# Grove_-_UV_Sensor_v1_0.net
KiCad netlist of a schematic drawn in EAGLE
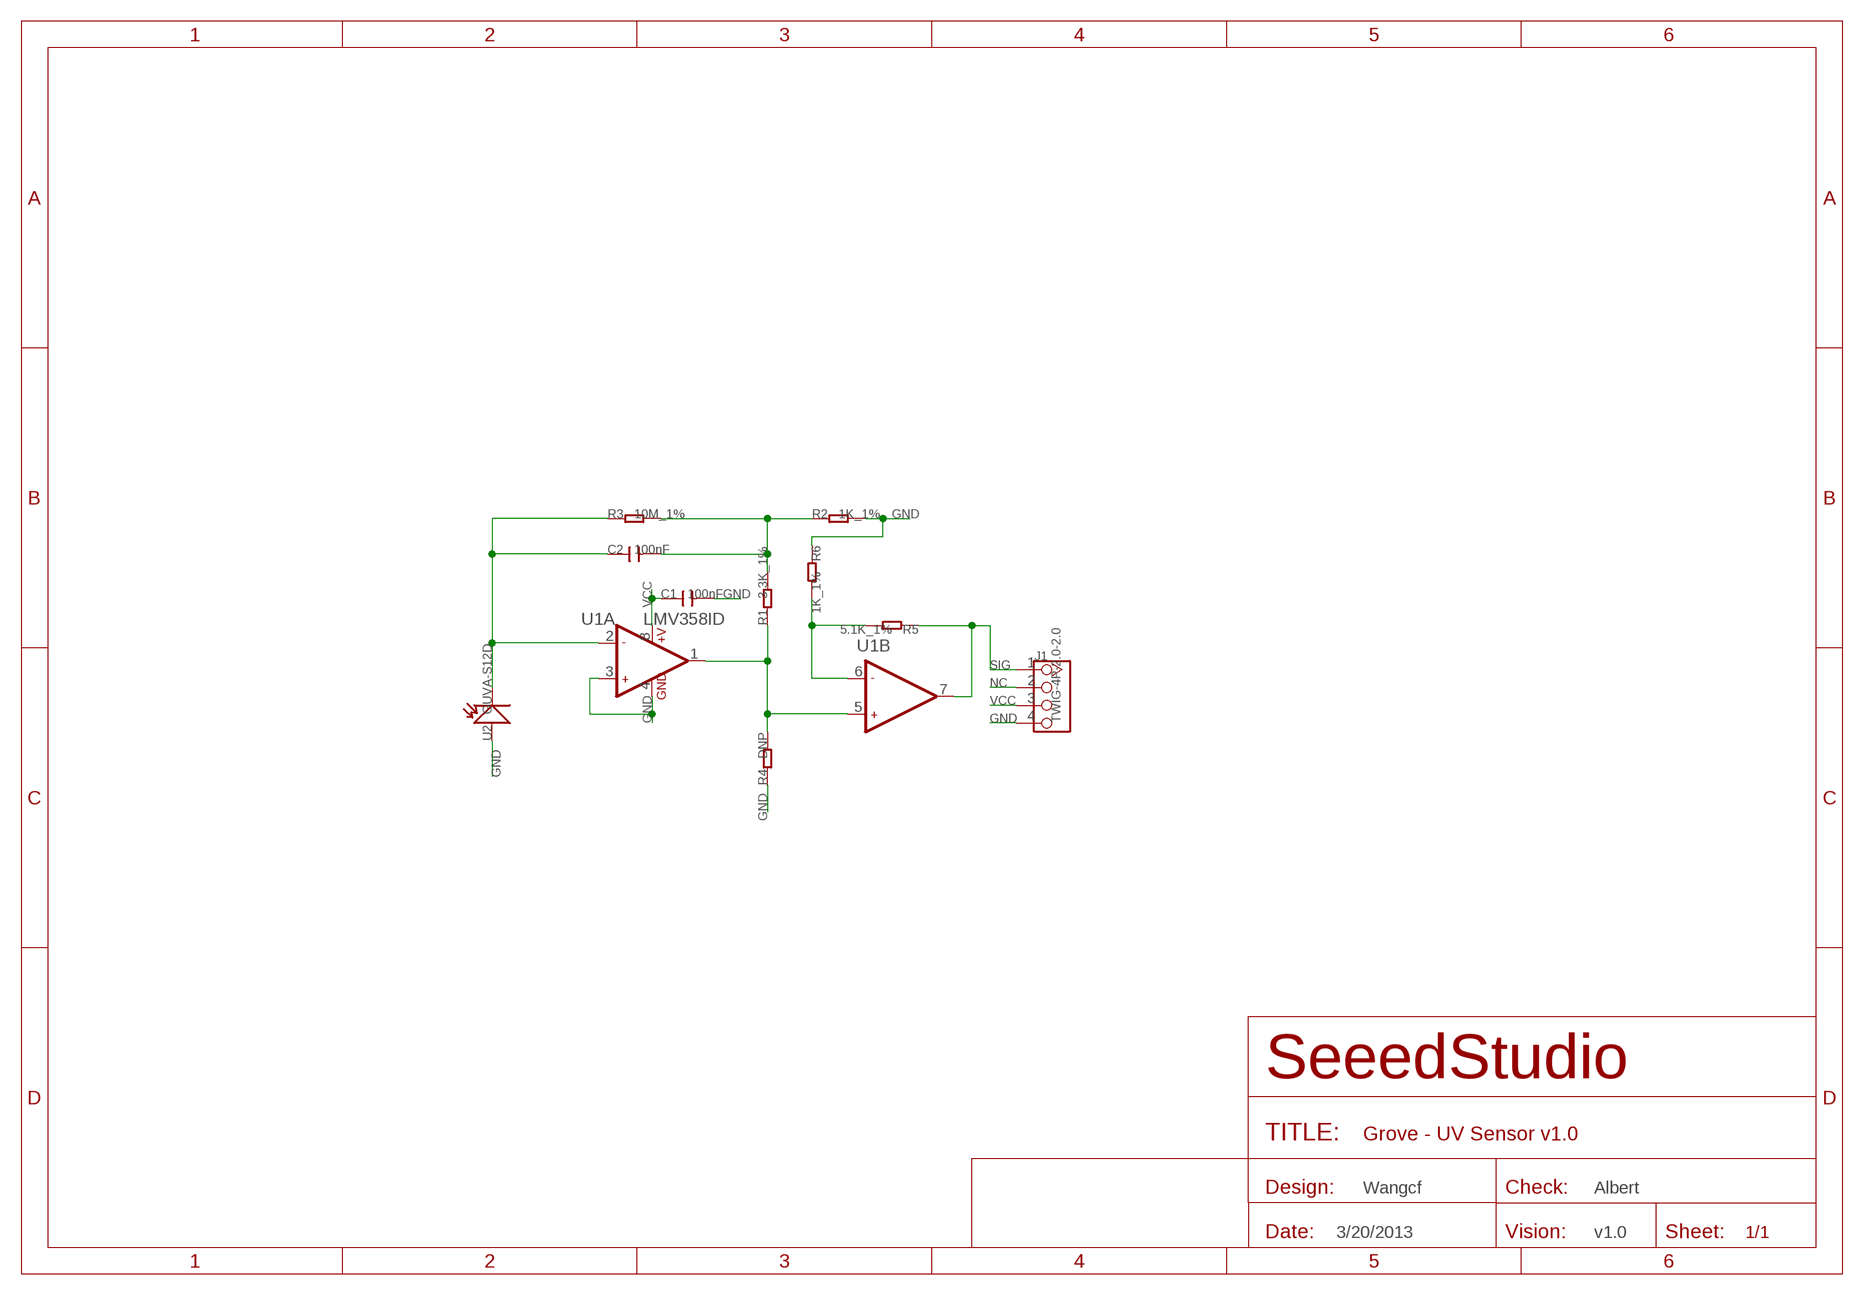
[diagram p0: schematic, sheet 1]

(export (version "E")
  (design (tool "Eeschema 10.0.6"))
  (components
    (comp (ref "C1")
      (value "100nF")
      (footprint "eagle-import:C0603")
      (libsource (lib "eagle-import") (part "C-0603"))
    )
    (comp (ref "C2")
      (value "100nF")
      (footprint "eagle-import:C0603")
      (libsource (lib "eagle-import") (part "C-0603"))
    )
    (comp (ref "J1")
      (value "TWIG-4P-2.0-2.0")
      (footprint "eagle-import:4P-2.0")
      (libsource (lib "eagle-import") (part "TWIG-4P-2.0-2.0"))
    )
    (comp (ref "R1")
      (value "3.3K_1%")
      (footprint "eagle-import:R0603")
      (libsource (lib "eagle-import") (part "R-0603"))
    )
    (comp (ref "R2")
      (value "1K_1%")
      (footprint "eagle-import:R0603")
      (libsource (lib "eagle-import") (part "R-0603"))
    )
    (comp (ref "R3")
      (value "10M_1%")
      (footprint "eagle-import:R0603")
      (libsource (lib "eagle-import") (part "R-0603"))
    )
    (comp (ref "R4")
      (value "DNP")
      (footprint "eagle-import:R0603")
      (libsource (lib "eagle-import") (part "R-0603"))
    )
    (comp (ref "R5")
      (value "5.1K_1%")
      (footprint "eagle-import:R0603")
      (libsource (lib "eagle-import") (part "R-0603"))
    )
    (comp (ref "R6")
      (value "1K_1%")
      (footprint "eagle-import:R0603")
      (libsource (lib "eagle-import") (part "R-0603"))
    )
    (comp (ref "U1")
      (value "LMV358ID")
      (footprint "eagle-import:SO08")
      (libsource (lib "eagle-import") (part "LMV358D"))
    )
    (comp (ref "U2")
      (value "GUVA-S12D")
      (footprint "eagle-import:LED-3528")
      (libsource (lib "eagle-import") (part "PHOTODIODE"))
    )
  )
  (nets
    (net (code "1") (name "/GND") (class "Default")
      (node (ref "C1") (pin "2") (pinfunction "2_2") (pintype "passive"))
      (node (ref "J1") (pin "4") (pinfunction "4_4") (pintype "bidirectional"))
      (node (ref "R2") (pin "2") (pinfunction "2_2") (pintype "passive"))
      (node (ref "R4") (pin "1") (pinfunction "1_1") (pintype "passive"))
      (node (ref "R6") (pin "1") (pinfunction "1_1") (pintype "passive"))
      (node (ref "U1") (pin "3") (pinfunction "+IN1_3") (pintype "input"))
      (node (ref "U1") (pin "4") (pinfunction "GND_4") (pintype "power_in"))
      (node (ref "U2") (pin "1") (pinfunction "+_1") (pintype "passive"))
    )
    (net (code "2") (name "/NC") (class "Default")
      (node (ref "J1") (pin "2") (pinfunction "2_2") (pintype "bidirectional"))
    )
    (net (code "3") (name "/SIG") (class "Default")
      (node (ref "R1") (pin "1") (pinfunction "1_1") (pintype "passive"))
      (node (ref "R4") (pin "2") (pinfunction "2_2") (pintype "passive"))
      (node (ref "U1") (pin "1") (pinfunction "OUT1_1") (pintype "output"))
      (node (ref "U1") (pin "5") (pinfunction "+IN2_5") (pintype "input"))
    )
    (net (code "4") (name "/VCC") (class "Default")
      (node (ref "C1") (pin "1") (pinfunction "1_1") (pintype "passive"))
      (node (ref "J1") (pin "3") (pinfunction "3_3") (pintype "bidirectional"))
      (node (ref "U1") (pin "8") (pinfunction "+V_8") (pintype "power_in"))
    )
    (net (code "5") (name "Net-(C2-Pad2)") (class "Default")
      (node (ref "C2") (pin "2") (pinfunction "2_2") (pintype "passive"))
      (node (ref "R1") (pin "2") (pinfunction "2_2") (pintype "passive"))
      (node (ref "R2") (pin "1") (pinfunction "1_1") (pintype "passive"))
      (node (ref "R3") (pin "2") (pinfunction "2_2") (pintype "passive"))
    )
    (net (code "6") (name "Net-(U1A--IN1)") (class "Default")
      (node (ref "C2") (pin "1") (pinfunction "1_1") (pintype "passive"))
      (node (ref "R3") (pin "1") (pinfunction "1_1") (pintype "passive"))
      (node (ref "U1") (pin "2") (pinfunction "-IN1_2") (pintype "input"))
      (node (ref "U2") (pin "2") (pinfunction "-_2") (pintype "passive"))
    )
    (net (code "7") (name "Net-(U1B--IN2)") (class "Default")
      (node (ref "R5") (pin "2") (pinfunction "2_2") (pintype "passive"))
      (node (ref "R6") (pin "2") (pinfunction "2_2") (pintype "passive"))
      (node (ref "U1") (pin "6") (pinfunction "-IN2_6") (pintype "input"))
    )
    (net (code "8") (name "Net-(U1B-OUT2)") (class "Default")
      (node (ref "J1") (pin "1") (pinfunction "1_1") (pintype "bidirectional"))
      (node (ref "R5") (pin "1") (pinfunction "1_1") (pintype "passive"))
      (node (ref "U1") (pin "7") (pinfunction "OUT2_7") (pintype "output"))
    )
  )
)
